# BM_LTC2943.net
KiCad netlist of a schematic drawn in Altium Designer
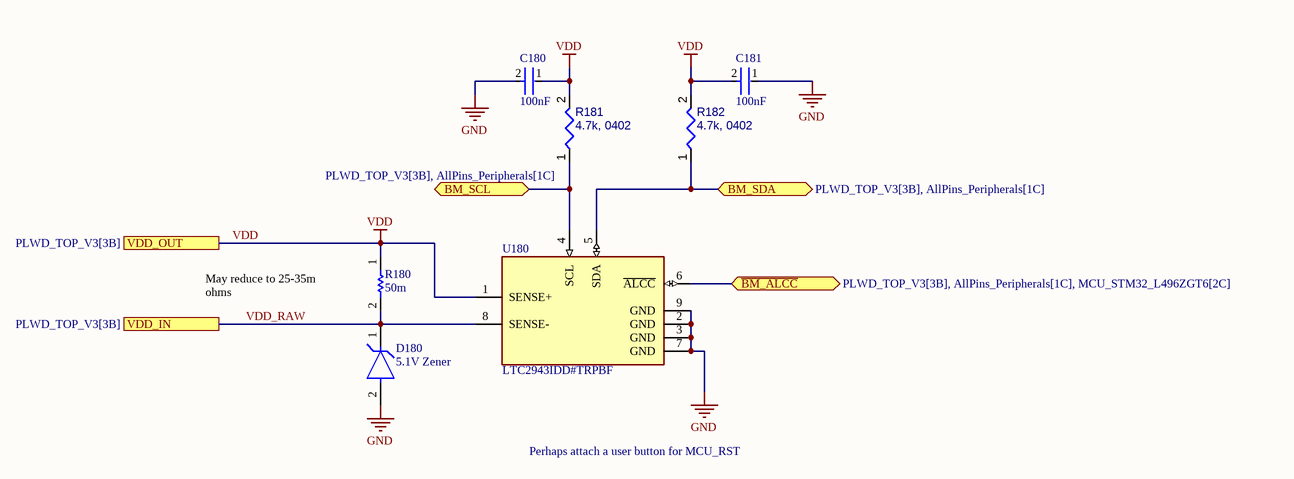
[diagram p0: BM_LTC2943.SchDoc]

(export (version "E")
  (design (tool "Eeschema 10.0.6"))
  (components
    (comp (ref "C180")
      (value "100nF")
      (footprint "FP-GRM15-MFG")
      (description "CAP CER 0.1UF 16V X7R 0402")
      (fields (field (name "MANUFACTURER PART NUMBER") "GRM155R71C104KA88D") (field (name "TOLERANCE") "10%"))
      (libsource (lib "Altium Content Vault") (part "236180d848d6139a670b325ea6854c9"))
    )
    (comp (ref "C181")
      (value "100nF")
      (footprint "FP-GRM15-MFG")
      (description "CAP CER 0.1UF 16V X7R 0402")
      (fields (field (name "MANUFACTURER PART NUMBER") "GRM155R71C104KA88D") (field (name "TOLERANCE") "10%"))
      (libsource (lib "Altium Content Vault") (part "236180d848d6139a670b325ea6854c9"))
    )
    (comp (ref "D180")
      (value "5.1V Zener")
      (footprint "FP-SOD123-MFG")
      (description "DIODE ZENER 5.1V 500MW SOD123")
      (fields
        (field (name "MANUFACTURER PART NUMBER") "BZT52C5V1-7-F")
        (field (name "OCTOPART") "https://octopart.com/bzt52c5v1-7-f-diodes+inc.-326718")
      )
      (libsource (lib "Altium Content Vault") (part "f813f71cba58e380607f5dd3caf9714"))
    )
    (comp (ref "R180")
      (value "50m")
      (footprint "RESC1608X55X30NL15T15")
      (fields (field (name "MANUFACTURER") "Panasonic") (field (name "PART NUMBER") "ERJ-L03KF50MV"))
      (libsource (lib "Altium Content Vault") (part "RES"))
    )
    (comp (ref "R181")
      (value "4.7k, 0402")
      (footprint "RESC0402(1005)_L")
      (description "Chip Resistor, 4,7 kOhms, +/-1 %, 63 mW, -55 to 155 degC, 0402")
      (fields (field (name "POWER") "63mW") (field (name "TOLERANCE") "1%"))
      (libsource (lib "Carleton University") (part "RES-2"))
    )
    (comp (ref "R182")
      (value "4.7k, 0402")
      (footprint "RESC0402(1005)_L")
      (description "Chip Resistor, 4,7 kOhms, +/-1 %, 63 mW, -55 to 155 degC, 0402")
      (fields (field (name "POWER") "63mW") (field (name "TOLERANCE") "1%"))
      (libsource (lib "Carleton University") (part "RES-2"))
    )
    (comp (ref "U180")
      (value "LTC2943IDD#TRPBF")
      (footprint "FP-DD-8-05-08-1698-IPC_B")
      (description "IC BATT MONITOR MULTI-CHEM 8DFN")
      (libsource (lib "Altium Content Vault") (part "886febee6aeca4f95c872c95bb57c34"))
    )
  )
  (nets
    (net (code "1") (name "/BM_SCL") (class "Default")
      (node (ref "R181") (pin "1") (pinfunction "1_1") (pintype "passive"))
      (node (ref "U180") (pin "4") (pinfunction "SCL_4") (pintype "input"))
    )
    (net (code "2") (name "/BM_SDA") (class "Default")
      (node (ref "R182") (pin "1") (pinfunction "1_1") (pintype "passive"))
      (node (ref "U180") (pin "5") (pinfunction "SDA_5") (pintype "bidirectional"))
    )
    (net (code "3") (name "/VDD_RAW") (class "Default")
      (node (ref "D180") (pin "1") (pinfunction "C_1") (pintype "passive"))
      (node (ref "R180") (pin "2") (pinfunction "2_2") (pintype "passive"))
      (node (ref "U180") (pin "8") (pinfunction "SENSE-_8") (pintype "passive"))
    )
    (net (code "4") (name "/~{BM_ALCC}") (class "Default")
      (node (ref "U180") (pin "6") (pinfunction "~{ALCC}_6") (pintype "bidirectional"))
    )
    (net (code "5") (name "GND") (class "Default")
      (node (ref "C180") (pin "2") (pinfunction "2_2") (pintype "passive"))
      (node (ref "C181") (pin "1") (pinfunction "1_1") (pintype "passive"))
      (node (ref "D180") (pin "2") (pinfunction "A_2") (pintype "passive"))
      (node (ref "U180") (pin "2") (pinfunction "GND_2") (pintype "power_in"))
      (node (ref "U180") (pin "3") (pinfunction "GND_3") (pintype "power_in"))
      (node (ref "U180") (pin "7") (pinfunction "GND_7") (pintype "power_in"))
      (node (ref "U180") (pin "9") (pinfunction "GND_9") (pintype "power_in"))
    )
    (net (code "6") (name "VDD") (class "Default")
      (node (ref "C180") (pin "1") (pinfunction "1_1") (pintype "passive"))
      (node (ref "C181") (pin "2") (pinfunction "2_2") (pintype "passive"))
      (node (ref "R180") (pin "1") (pinfunction "1_1") (pintype "passive"))
      (node (ref "R181") (pin "2") (pinfunction "2_2") (pintype "passive"))
      (node (ref "R182") (pin "2") (pinfunction "2_2") (pintype "passive"))
      (node (ref "U180") (pin "1") (pinfunction "SENSE+_1") (pintype "passive"))
    )
  )
)
